# 25mm_battery_board.net
KiCad netlist of a schematic drawn in EAGLE
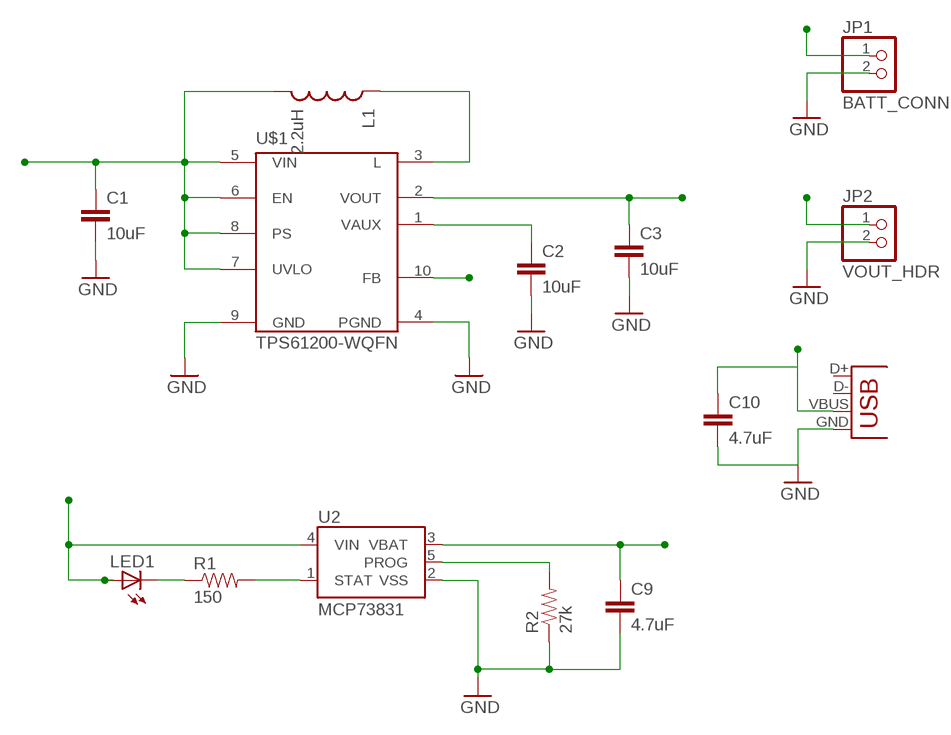
[diagram p0: schematic, sheet 1]

(export (version "E")
  (design (tool "Eeschema 10.0.6"))
  (components
    (comp (ref "C1")
      (value "10uF")
      (footprint "eagle-import:1206")
      (libsource (lib "eagle-import") (part "CAP1206"))
    )
    (comp (ref "C2")
      (value "10uF")
      (footprint "eagle-import:1206")
      (libsource (lib "eagle-import") (part "CAP1206"))
    )
    (comp (ref "C3")
      (value "10uF")
      (footprint "eagle-import:1206")
      (libsource (lib "eagle-import") (part "CAP1206"))
    )
    (comp (ref "C9")
      (value "4.7uF")
      (footprint "eagle-import:1206")
      (libsource (lib "eagle-import") (part "CAP1206"))
    )
    (comp (ref "C10")
      (value "4.7uF")
      (footprint "eagle-import:1206")
      (libsource (lib "eagle-import") (part "CAP1206"))
    )
    (comp (ref "JP1")
      (value "BATT_CONN")
      (footprint "eagle-import:1X02")
      (libsource (lib "eagle-import") (part "PINHD-1X2"))
    )
    (comp (ref "JP2")
      (value "VOUT_HDR")
      (footprint "eagle-import:1X02")
      (libsource (lib "eagle-import") (part "PINHD-1X2"))
    )
    (comp (ref "L1")
      (value "2.2uH")
      (footprint "eagle-import:CDRH3D28")
      (libsource (lib "eagle-import") (part "INDUCTOR-"))
    )
    (comp (ref "LED1")
      (value "LED0603")
      (footprint "eagle-import:LED-0603")
      (libsource (lib "eagle-import") (part "LED0603"))
    )
    (comp (ref "R1")
      (value "150")
      (footprint "eagle-import:0805")
      (libsource (lib "eagle-import") (part "RESISTOR0805-RES"))
    )
    (comp (ref "R2")
      (value "27k")
      (footprint "eagle-import:0805")
      (libsource (lib "eagle-import") (part "RESISTOR0805-RES"))
    )
    (comp (ref "U$1")
      (value "TPS61200-WQFN")
      (footprint "eagle-import:QFN-10")
      (libsource (lib "eagle-import") (part "TPS61200-WQFN"))
    )
    (comp (ref "U2")
      (value "MCP73831")
      (footprint "eagle-import:SOT23-5")
      (libsource (lib "eagle-import") (part "MCP73831"))
    )
    (comp (ref "X1")
      (value "USBSMD")
      (footprint "eagle-import:USB-MINIB")
      (libsource (lib "eagle-import") (part "USBSMD"))
    )
  )
  (nets
    (net (code "1") (name "/VBATT") (class "Default")
      (node (ref "C1") (pin "1") (pinfunction "1_1") (pintype "passive"))
      (node (ref "C9") (pin "1") (pinfunction "1_1") (pintype "passive"))
      (node (ref "JP1") (pin "1") (pinfunction "1_1") (pintype "passive"))
      (node (ref "L1") (pin "2") (pinfunction "2_2") (pintype "passive"))
      (node (ref "U$1") (pin "5") (pinfunction "VIN_5") (pintype "bidirectional"))
      (node (ref "U$1") (pin "6") (pinfunction "EN_6") (pintype "bidirectional"))
      (node (ref "U$1") (pin "7") (pinfunction "UVLO_7") (pintype "bidirectional"))
      (node (ref "U$1") (pin "8") (pinfunction "PS_8") (pintype "bidirectional"))
      (node (ref "U2") (pin "3") (pinfunction "VBAT_3") (pintype "power_in"))
    )
    (net (code "2") (name "/VOUT") (class "Default")
      (node (ref "C3") (pin "1") (pinfunction "1_1") (pintype "passive"))
      (node (ref "JP2") (pin "1") (pinfunction "1_1") (pintype "passive"))
      (node (ref "U$1") (pin "10") (pinfunction "FB_10") (pintype "bidirectional"))
      (node (ref "U$1") (pin "2") (pinfunction "VOUT_2") (pintype "bidirectional"))
    )
    (net (code "3") (name "/VUSB") (class "Default")
      (node (ref "C10") (pin "1") (pinfunction "1_1") (pintype "passive"))
      (node (ref "LED1") (pin "A") (pinfunction "A_A") (pintype "passive"))
      (node (ref "U2") (pin "4") (pinfunction "VIN_4") (pintype "power_in"))
      (node (ref "X1") (pin "VBUS") (pinfunction "VBUS_VBUS") (pintype "bidirectional"))
    )
    (net (code "4") (name "GND") (class "Default")
      (node (ref "C1") (pin "2") (pinfunction "2_2") (pintype "passive"))
      (node (ref "C10") (pin "2") (pinfunction "2_2") (pintype "passive"))
      (node (ref "C2") (pin "2") (pinfunction "2_2") (pintype "passive"))
      (node (ref "C3") (pin "2") (pinfunction "2_2") (pintype "passive"))
      (node (ref "C9") (pin "2") (pinfunction "2_2") (pintype "passive"))
      (node (ref "JP1") (pin "2") (pinfunction "2_2") (pintype "passive"))
      (node (ref "JP2") (pin "2") (pinfunction "2_2") (pintype "passive"))
      (node (ref "R2") (pin "1") (pinfunction "1_1") (pintype "passive"))
      (node (ref "U$1") (pin "4") (pinfunction "PGND_4") (pintype "bidirectional"))
      (node (ref "U$1") (pin "9") (pinfunction "GND_9") (pintype "bidirectional"))
      (node (ref "U2") (pin "2") (pinfunction "VSS_2") (pintype "power_in"))
      (node (ref "X1") (pin "GND") (pinfunction "GND_GND") (pintype "bidirectional"))
    )
    (net (code "5") (name "Net-(LED1-PadC)") (class "Default")
      (node (ref "LED1") (pin "C") (pinfunction "C_C") (pintype "passive"))
      (node (ref "R1") (pin "1") (pinfunction "1_1") (pintype "passive"))
    )
    (net (code "6") (name "Net-(U$1-L)") (class "Default")
      (node (ref "L1") (pin "1") (pinfunction "1_1") (pintype "passive"))
      (node (ref "U$1") (pin "3") (pinfunction "L_3") (pintype "bidirectional"))
    )
    (net (code "7") (name "Net-(U$1-VAUX)") (class "Default")
      (node (ref "C2") (pin "1") (pinfunction "1_1") (pintype "passive"))
      (node (ref "U$1") (pin "1") (pinfunction "VAUX_1") (pintype "bidirectional"))
    )
    (net (code "8") (name "Net-(U2-PROG)") (class "Default")
      (node (ref "R2") (pin "2") (pinfunction "2_2") (pintype "passive"))
      (node (ref "U2") (pin "5") (pinfunction "PROG_5") (pintype "input"))
    )
    (net (code "9") (name "Net-(U2-STAT)") (class "Default")
      (node (ref "R1") (pin "2") (pinfunction "2_2") (pintype "passive"))
      (node (ref "U2") (pin "1") (pinfunction "STAT_1") (pintype "output"))
    )
    (net (code "10") (name "unconnected-(X1-PadD+)") (class "Default")
      (node (ref "X1") (pin "D+") (pinfunction "D+_D+") (pintype "bidirectional"))
    )
    (net (code "11") (name "unconnected-(X1-PadD-)") (class "Default")
      (node (ref "X1") (pin "D-") (pinfunction "D-_D-") (pintype "bidirectional"))
    )
  )
)
